# vdo_regulator.net
KiCad netlist of a schematic drawn in EAGLE
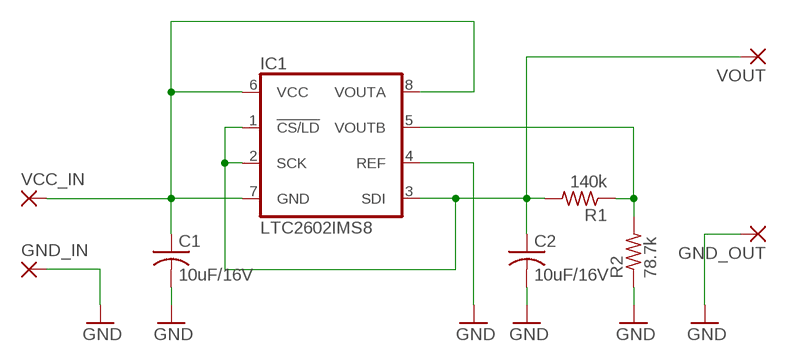
[diagram p0: schematic, sheet 1]

(export (version "E")
  (design (tool "Eeschema 10.0.6"))
  (components
    (comp (ref "C1")
      (value "10uF/16V")
      (footprint "eagle-import:C025-025X050")
      (libsource (lib "eagle-import") (part "C-US025-025X050"))
    )
    (comp (ref "C2")
      (value "10uF/16V")
      (footprint "eagle-import:C025-025X050")
      (libsource (lib "eagle-import") (part "C-US025-025X050"))
    )
    (comp (ref "GND_IN")
      (value "2,54/0,9")
      (footprint "eagle-import:2,54_0,9")
      (libsource (lib "eagle-import") (part "2,54/0,9"))
    )
    (comp (ref "GND_OUT")
      (value "2,54/0,9")
      (footprint "eagle-import:2,54_0,9")
      (libsource (lib "eagle-import") (part "2,54/0,9"))
    )
    (comp (ref "IC1")
      (value "LTC2602IMS8")
      (footprint "eagle-import:MSOP8")
      (libsource (lib "eagle-import") (part "LTC26MS802I"))
    )
    (comp (ref "R1")
      (value "140k")
      (footprint "eagle-import:0309_10")
      (libsource (lib "eagle-import") (part "R-US_0309/10"))
    )
    (comp (ref "R2")
      (value "78.7k")
      (footprint "eagle-import:0309_10")
      (libsource (lib "eagle-import") (part "R-US_0309/10"))
    )
    (comp (ref "VCC_IN")
      (value "2,54/0,9")
      (footprint "eagle-import:2,54_0,9")
      (libsource (lib "eagle-import") (part "2,54/0,9"))
    )
    (comp (ref "VOUT")
      (value "2,54/0,9")
      (footprint "eagle-import:2,54_0,9")
      (libsource (lib "eagle-import") (part "2,54/0,9"))
    )
  )
  (nets
    (net (code "1") (name "GND") (class "Default")
      (node (ref "C1") (pin "2") (pinfunction "2_2") (pintype "passive"))
      (node (ref "C2") (pin "2") (pinfunction "2_2") (pintype "passive"))
      (node (ref "GND_IN") (pin "1") (pinfunction "P_1") (pintype "passive"))
      (node (ref "GND_OUT") (pin "1") (pinfunction "P_1") (pintype "passive"))
      (node (ref "IC1") (pin "4") (pinfunction "REF_4") (pintype "input"))
      (node (ref "R2") (pin "1") (pinfunction "1_1") (pintype "passive"))
    )
    (net (code "2") (name "Net-(IC1-GND)") (class "Default")
      (node (ref "C1") (pin "1") (pinfunction "1_1") (pintype "passive"))
      (node (ref "IC1") (pin "6") (pinfunction "VCC_6") (pintype "power_in"))
      (node (ref "IC1") (pin "7") (pinfunction "GND_7") (pintype "power_in"))
      (node (ref "IC1") (pin "8") (pinfunction "VOUTA_8") (pintype "output"))
      (node (ref "VCC_IN") (pin "1") (pinfunction "P_1") (pintype "passive"))
    )
    (net (code "3") (name "Net-(IC1-SCK)") (class "Default")
      (node (ref "C2") (pin "1") (pinfunction "1_1") (pintype "passive"))
      (node (ref "IC1") (pin "1") (pinfunction "~{CS/LD}_1") (pintype "input"))
      (node (ref "IC1") (pin "2") (pinfunction "SCK_2") (pintype "input"))
      (node (ref "IC1") (pin "3") (pinfunction "SDI_3") (pintype "input"))
      (node (ref "R1") (pin "2") (pinfunction "2_2") (pintype "passive"))
      (node (ref "VOUT") (pin "1") (pinfunction "P_1") (pintype "passive"))
    )
    (net (code "4") (name "Net-(IC1-VOUTB)") (class "Default")
      (node (ref "IC1") (pin "5") (pinfunction "VOUTB_5") (pintype "output"))
      (node (ref "R1") (pin "1") (pinfunction "1_1") (pintype "passive"))
      (node (ref "R2") (pin "2") (pinfunction "2_2") (pintype "passive"))
    )
  )
)
